# GasSensorModule_v1_0.net
KiCad netlist of a schematic drawn in EAGLE
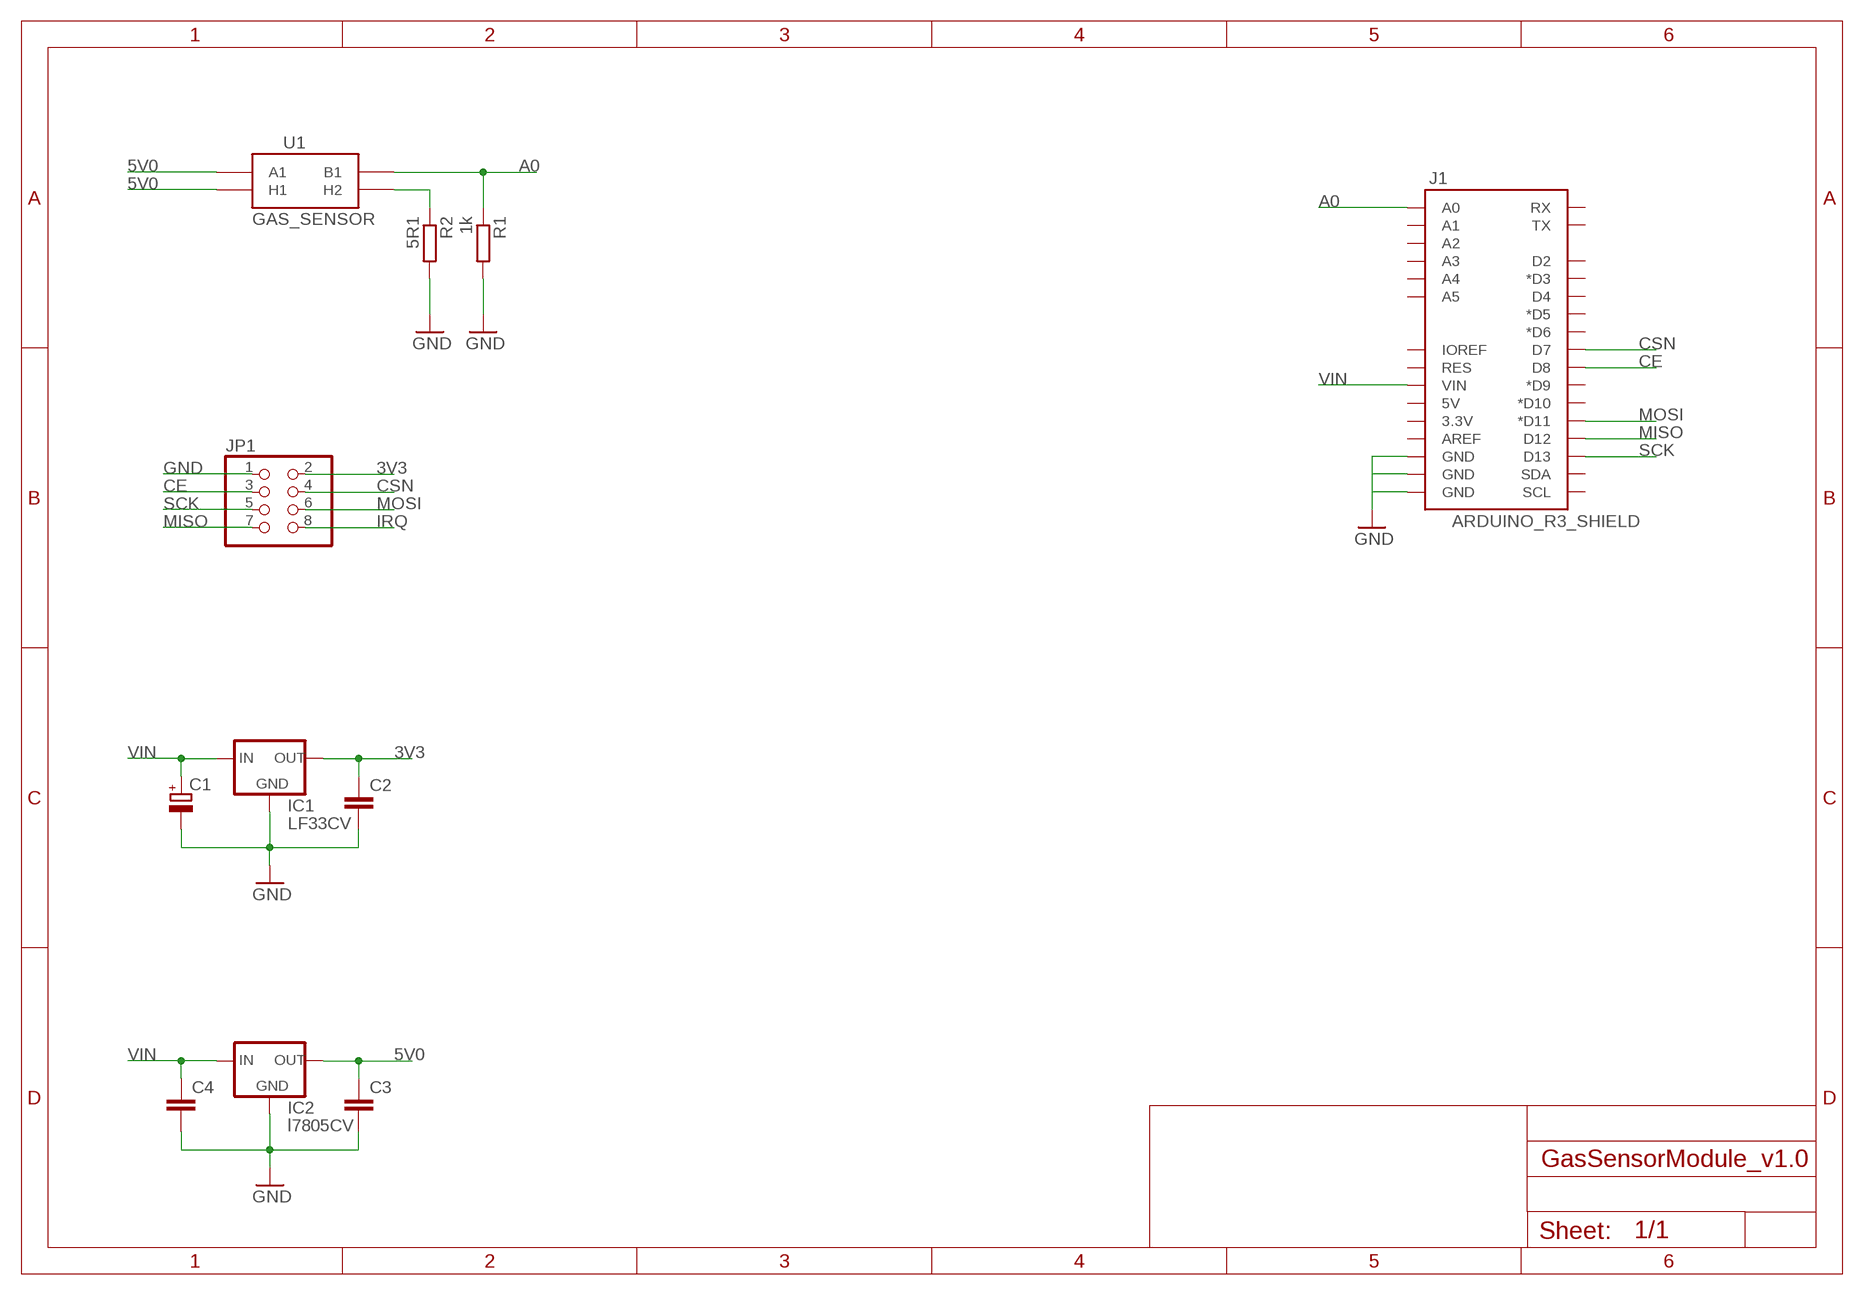
[diagram p0: schematic, sheet 1]

(export (version "E")
  (design (tool "Eeschema 10.0.6"))
  (components
    (comp (ref "C1")
      (value "CPOL-EUE2,5-6E")
      (footprint "eagle-import:E2,5-6E")
      (libsource (lib "eagle-import") (part "CPOL-EUE2,5-6E"))
    )
    (comp (ref "C2")
      (value "C-EU025-025X050")
      (footprint "eagle-import:C025-025X050")
      (libsource (lib "eagle-import") (part "C-EU025-025X050"))
    )
    (comp (ref "C3")
      (value "C-EU025-025X050")
      (footprint "eagle-import:C025-025X050")
      (libsource (lib "eagle-import") (part "C-EU025-025X050"))
    )
    (comp (ref "C4")
      (value "C-EU025-025X050")
      (footprint "eagle-import:C025-025X050")
      (libsource (lib "eagle-import") (part "C-EU025-025X050"))
    )
    (comp (ref "IC1")
      (value "LF33CV")
      (footprint "eagle-import:78XXS")
      (libsource (lib "eagle-import") (part "78XXS"))
    )
    (comp (ref "IC2")
      (value "l7805CV")
      (footprint "eagle-import:78XXS")
      (libsource (lib "eagle-import") (part "78XXS"))
    )
    (comp (ref "J1")
      (value "ARDUINO_R3_SHIELD")
      (footprint "eagle-import:UNO_R3_SHIELD")
      (libsource (lib "eagle-import") (part "ARDUINO_R3_SHIELD"))
    )
    (comp (ref "JP1")
      (value "PINHD-2X4")
      (footprint "eagle-import:2X04")
      (libsource (lib "eagle-import") (part "PINHD-2X4"))
    )
    (comp (ref "R1")
      (value "1k")
      (footprint "eagle-import:0207_10")
      (libsource (lib "eagle-import") (part "R-EU_0207/10"))
    )
    (comp (ref "R2")
      (value "5R1")
      (footprint "eagle-import:0207_10")
      (libsource (lib "eagle-import") (part "R-EU_0207/10"))
    )
    (comp (ref "U1")
      (value "GAS_SENSOR")
      (footprint "eagle-import:MQ-3")
      (libsource (lib "eagle-import") (part "GAS_SENSOR"))
    )
  )
  (nets
    (net (code "1") (name "/3V3") (class "Default")
      (node (ref "C2") (pin "1") (pinfunction "1_1") (pintype "passive"))
      (node (ref "IC1") (pin "OUT") (pinfunction "OUT_OUT") (pintype "passive"))
      (node (ref "JP1") (pin "2") (pinfunction "2_2") (pintype "passive"))
    )
    (net (code "2") (name "/5V0") (class "Default")
      (node (ref "C3") (pin "1") (pinfunction "1_1") (pintype "passive"))
      (node (ref "IC2") (pin "OUT") (pinfunction "OUT_OUT") (pintype "passive"))
      (node (ref "U1") (pin "A1") (pinfunction "A1_A1") (pintype "bidirectional"))
      (node (ref "U1") (pin "HA") (pinfunction "H1_HA") (pintype "bidirectional"))
    )
    (net (code "3") (name "/A0") (class "Default")
      (node (ref "J1") (pin "A0") (pinfunction "A0_A0") (pintype "bidirectional"))
      (node (ref "R1") (pin "1") (pinfunction "1_1") (pintype "passive"))
      (node (ref "U1") (pin "B1") (pinfunction "B1_B1") (pintype "bidirectional"))
    )
    (net (code "4") (name "/CE") (class "Default")
      (node (ref "J1") (pin "D8") (pinfunction "D8_D8") (pintype "bidirectional"))
      (node (ref "JP1") (pin "3") (pinfunction "3_3") (pintype "passive"))
    )
    (net (code "5") (name "/CSN") (class "Default")
      (node (ref "J1") (pin "D7") (pinfunction "D7_D7") (pintype "bidirectional"))
      (node (ref "JP1") (pin "4") (pinfunction "4_4") (pintype "passive"))
    )
    (net (code "6") (name "/IRQ") (class "Default")
      (node (ref "JP1") (pin "8") (pinfunction "8_8") (pintype "passive"))
    )
    (net (code "7") (name "/MISO") (class "Default")
      (node (ref "J1") (pin "D12") (pinfunction "D12_D12") (pintype "bidirectional"))
      (node (ref "JP1") (pin "7") (pinfunction "7_7") (pintype "passive"))
    )
    (net (code "8") (name "/MOSI") (class "Default")
      (node (ref "J1") (pin "D11") (pinfunction "*D11_D11") (pintype "bidirectional"))
      (node (ref "JP1") (pin "6") (pinfunction "6_6") (pintype "passive"))
    )
    (net (code "9") (name "/SCK") (class "Default")
      (node (ref "J1") (pin "D13") (pinfunction "D13_D13") (pintype "bidirectional"))
      (node (ref "JP1") (pin "5") (pinfunction "5_5") (pintype "passive"))
    )
    (net (code "10") (name "/VIN") (class "Default")
      (node (ref "C1") (pin "+") (pinfunction "+_+") (pintype "passive"))
      (node (ref "C4") (pin "1") (pinfunction "1_1") (pintype "passive"))
      (node (ref "IC1") (pin "IN") (pinfunction "IN_IN") (pintype "input"))
      (node (ref "IC2") (pin "IN") (pinfunction "IN_IN") (pintype "input"))
      (node (ref "J1") (pin "VIN") (pinfunction "VIN_VIN") (pintype "bidirectional"))
    )
    (net (code "11") (name "GND") (class "Default")
      (node (ref "C1") (pin "-") (pinfunction "-_-") (pintype "passive"))
      (node (ref "C2") (pin "2") (pinfunction "2_2") (pintype "passive"))
      (node (ref "C3") (pin "2") (pinfunction "2_2") (pintype "passive"))
      (node (ref "C4") (pin "2") (pinfunction "2_2") (pintype "passive"))
      (node (ref "IC1") (pin "GND") (pinfunction "GND_GND") (pintype "input"))
      (node (ref "IC2") (pin "GND") (pinfunction "GND_GND") (pintype "input"))
      (node (ref "J1") (pin "GND@0") (pinfunction "GND_GND@0") (pintype "bidirectional"))
      (node (ref "J1") (pin "GND@1") (pinfunction "GND_GND@1") (pintype "bidirectional"))
      (node (ref "J1") (pin "GND@2") (pinfunction "GND_GND@2") (pintype "bidirectional"))
      (node (ref "JP1") (pin "1") (pinfunction "1_1") (pintype "passive"))
      (node (ref "R1") (pin "2") (pinfunction "2_2") (pintype "passive"))
      (node (ref "R2") (pin "2") (pinfunction "2_2") (pintype "passive"))
    )
    (net (code "12") (name "Net-(U1-H2)") (class "Default")
      (node (ref "R2") (pin "1") (pinfunction "1_1") (pintype "passive"))
      (node (ref "U1") (pin "HB") (pinfunction "H2_HB") (pintype "bidirectional"))
    )
    (net (code "13") (name "unconnected-(J1-*D3-PadD3)") (class "Default")
      (node (ref "J1") (pin "D3") (pinfunction "*D3_D3") (pintype "bidirectional"))
    )
    (net (code "14") (name "unconnected-(J1-*D5-PadD5)") (class "Default")
      (node (ref "J1") (pin "D5") (pinfunction "*D5_D5") (pintype "bidirectional"))
    )
    (net (code "15") (name "unconnected-(J1-*D6-PadD6)") (class "Default")
      (node (ref "J1") (pin "D6") (pinfunction "*D6_D6") (pintype "bidirectional"))
    )
    (net (code "16") (name "unconnected-(J1-*D9-PadD9)") (class "Default")
      (node (ref "J1") (pin "D9") (pinfunction "*D9_D9") (pintype "bidirectional"))
    )
    (net (code "17") (name "unconnected-(J1-*D10-PadD10)") (class "Default")
      (node (ref "J1") (pin "D10") (pinfunction "*D10_D10") (pintype "bidirectional"))
    )
    (net (code "18") (name "unconnected-(J1-Pad3.3V)") (class "Default")
      (node (ref "J1") (pin "3.3V") (pinfunction "3.3V_3.3V") (pintype "bidirectional"))
    )
    (net (code "19") (name "unconnected-(J1-Pad5V)") (class "Default")
      (node (ref "J1") (pin "5V") (pinfunction "5V_5V") (pintype "bidirectional"))
    )
    (net (code "20") (name "unconnected-(J1-PadA1)") (class "Default")
      (node (ref "J1") (pin "A1") (pinfunction "A1_A1") (pintype "bidirectional"))
    )
    (net (code "21") (name "unconnected-(J1-PadA2)") (class "Default")
      (node (ref "J1") (pin "A2") (pinfunction "A2_A2") (pintype "bidirectional"))
    )
    (net (code "22") (name "unconnected-(J1-PadA3)") (class "Default")
      (node (ref "J1") (pin "A3") (pinfunction "A3_A3") (pintype "bidirectional"))
    )
    (net (code "23") (name "unconnected-(J1-PadA4)") (class "Default")
      (node (ref "J1") (pin "A4") (pinfunction "A4_A4") (pintype "bidirectional"))
    )
    (net (code "24") (name "unconnected-(J1-PadA5)") (class "Default")
      (node (ref "J1") (pin "A5") (pinfunction "A5_A5") (pintype "bidirectional"))
    )
    (net (code "25") (name "unconnected-(J1-PadAREF)") (class "Default")
      (node (ref "J1") (pin "AREF") (pinfunction "AREF_AREF") (pintype "bidirectional"))
    )
    (net (code "26") (name "unconnected-(J1-PadD2)") (class "Default")
      (node (ref "J1") (pin "D2") (pinfunction "D2_D2") (pintype "bidirectional"))
    )
    (net (code "27") (name "unconnected-(J1-PadD4)") (class "Default")
      (node (ref "J1") (pin "D4") (pinfunction "D4_D4") (pintype "bidirectional"))
    )
    (net (code "28") (name "unconnected-(J1-PadIOREF)") (class "Default")
      (node (ref "J1") (pin "IOREF") (pinfunction "IOREF_IOREF") (pintype "bidirectional"))
    )
    (net (code "29") (name "unconnected-(J1-PadRES)") (class "Default")
      (node (ref "J1") (pin "RES") (pinfunction "RES_RES") (pintype "bidirectional"))
    )
    (net (code "30") (name "unconnected-(J1-PadRX)") (class "Default")
      (node (ref "J1") (pin "RX") (pinfunction "RX_RX") (pintype "bidirectional"))
    )
    (net (code "31") (name "unconnected-(J1-PadSCL)") (class "Default")
      (node (ref "J1") (pin "SCL") (pinfunction "SCL_SCL") (pintype "bidirectional"))
    )
    (net (code "32") (name "unconnected-(J1-PadSDA)") (class "Default")
      (node (ref "J1") (pin "SDA") (pinfunction "SDA_SDA") (pintype "bidirectional"))
    )
    (net (code "33") (name "unconnected-(J1-PadTX)") (class "Default")
      (node (ref "J1") (pin "TX") (pinfunction "TX_TX") (pintype "bidirectional"))
    )
  )
)
